# GigaVGA666PS2.net
KiCad netlist of a schematic drawn in EasyEDA Pro
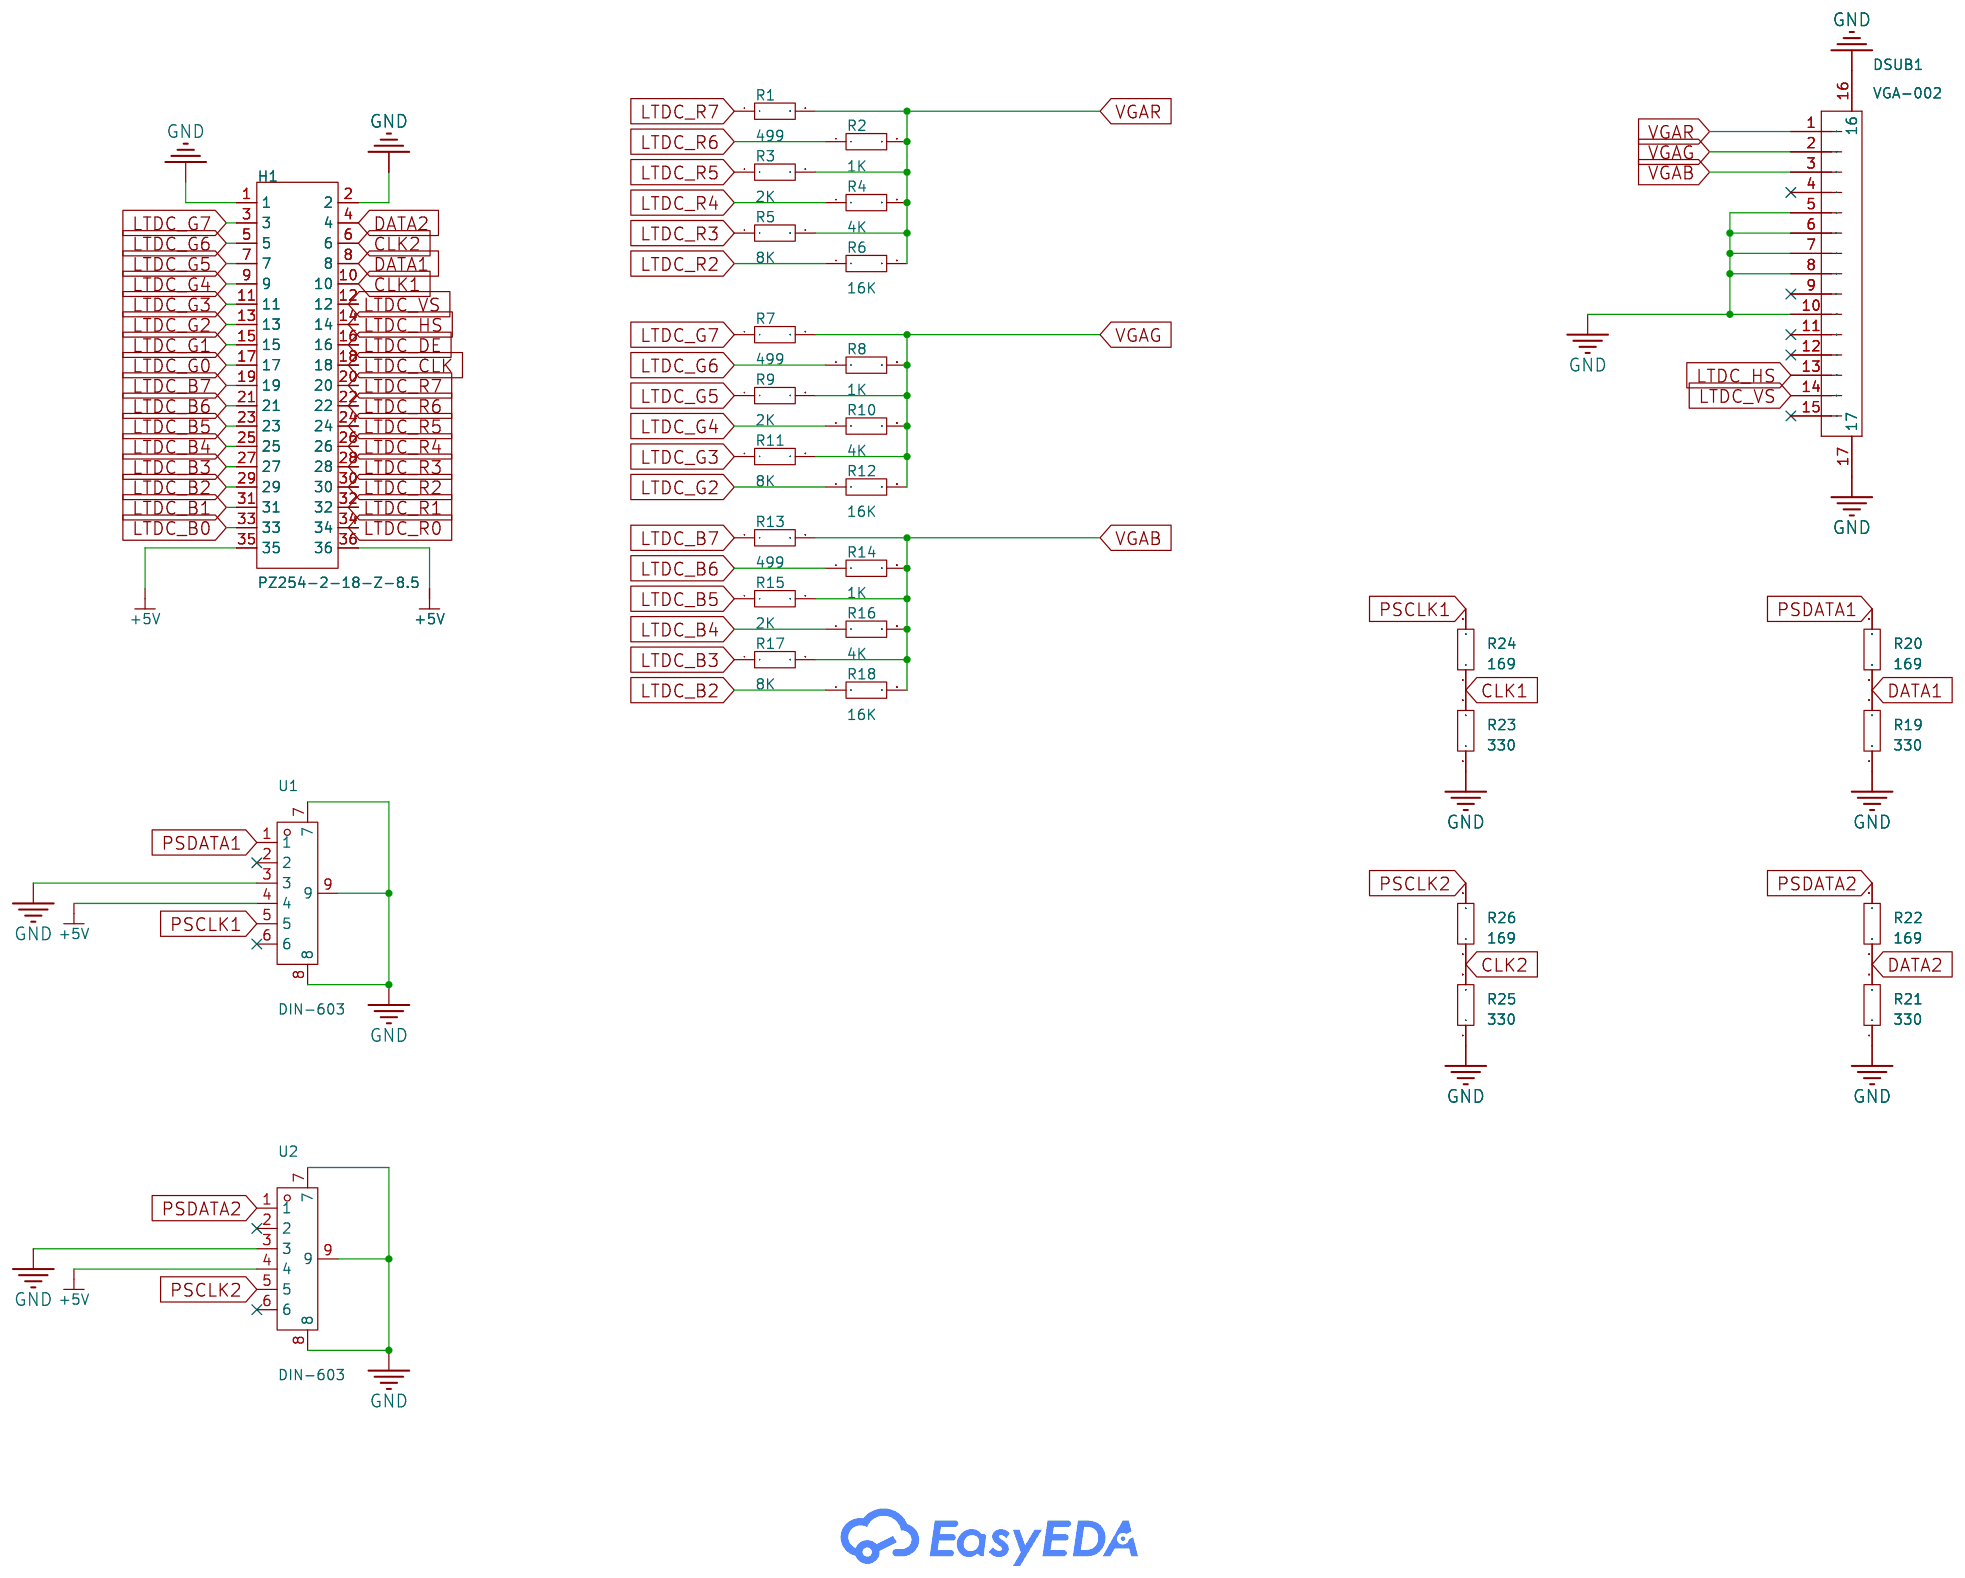
[diagram p0: schematic sheet]

(export (version "E")
  (design (tool "Eeschema 10.0.6"))
  (components
    (comp (ref "DSUB1")
      (value "VGA-002")
      (footprint "easyedapro:D-SUB-TH_VGA-002")
      (fields (field (name "Manufacturer") "BOOMELE(博穆精密)"))
      (libsource (lib "easyedapro") (part "VGA-002"))
    )
    (comp (ref "H1")
      (value "PZ254-2-18-Z-8.5")
      (footprint "easyedapro:HDR-TH_36P-P2.54-V-M-R2-C18-S2.54")
      (fields (field (name "Manufacturer") "HCTL(华灿天禄)"))
      (libsource (lib "easyedapro") (part "PZ254-2-18-Z-8.5"))
    )
    (comp (ref "R1") (value "499") (footprint "easyedapro:R0603") (libsource (lib "easyedapro") (part "Res")))
    (comp (ref "R2") (value "1K") (footprint "easyedapro:R0603") (libsource (lib "easyedapro") (part "Res")))
    (comp (ref "R3") (value "2K") (footprint "easyedapro:R0603") (libsource (lib "easyedapro") (part "Res")))
    (comp (ref "R4") (value "4K") (footprint "easyedapro:R0603") (libsource (lib "easyedapro") (part "Res")))
    (comp (ref "R5") (value "8K") (footprint "easyedapro:R0603") (libsource (lib "easyedapro") (part "Res")))
    (comp (ref "R6") (value "16K") (footprint "easyedapro:R0603") (libsource (lib "easyedapro") (part "Res")))
    (comp (ref "R7") (value "499") (footprint "easyedapro:R0603") (libsource (lib "easyedapro") (part "Res")))
    (comp (ref "R8") (value "1K") (footprint "easyedapro:R0603") (libsource (lib "easyedapro") (part "Res")))
    (comp (ref "R9") (value "2K") (footprint "easyedapro:R0603") (libsource (lib "easyedapro") (part "Res")))
    (comp (ref "R10") (value "4K") (footprint "easyedapro:R0603") (libsource (lib "easyedapro") (part "Res")))
    (comp (ref "R11") (value "8K") (footprint "easyedapro:R0603") (libsource (lib "easyedapro") (part "Res")))
    (comp (ref "R12")
      (value "16K")
      (footprint "easyedapro:R0603")
      (libsource (lib "easyedapro") (part "Res"))
    )
    (comp (ref "R13")
      (value "499")
      (footprint "easyedapro:R0603")
      (libsource (lib "easyedapro") (part "Res"))
    )
    (comp (ref "R14") (value "1K") (footprint "easyedapro:R0603") (libsource (lib "easyedapro") (part "Res")))
    (comp (ref "R15") (value "2K") (footprint "easyedapro:R0603") (libsource (lib "easyedapro") (part "Res")))
    (comp (ref "R16") (value "4K") (footprint "easyedapro:R0603") (libsource (lib "easyedapro") (part "Res")))
    (comp (ref "R17") (value "8K") (footprint "easyedapro:R0603") (libsource (lib "easyedapro") (part "Res")))
    (comp (ref "R18")
      (value "16K")
      (footprint "easyedapro:R0603")
      (libsource (lib "easyedapro") (part "Res"))
    )
    (comp (ref "R19")
      (value "330")
      (footprint "easyedapro:R0603")
      (libsource (lib "easyedapro") (part "Res"))
    )
    (comp (ref "R20")
      (value "169")
      (footprint "easyedapro:R0603")
      (libsource (lib "easyedapro") (part "Res"))
    )
    (comp (ref "R21")
      (value "330")
      (footprint "easyedapro:R0603")
      (libsource (lib "easyedapro") (part "Res"))
    )
    (comp (ref "R22")
      (value "169")
      (footprint "easyedapro:R0603")
      (libsource (lib "easyedapro") (part "Res"))
    )
    (comp (ref "R23")
      (value "330")
      (footprint "easyedapro:R0603")
      (libsource (lib "easyedapro") (part "Res"))
    )
    (comp (ref "R24")
      (value "169")
      (footprint "easyedapro:R0603")
      (libsource (lib "easyedapro") (part "Res"))
    )
    (comp (ref "R25")
      (value "330")
      (footprint "easyedapro:R0603")
      (libsource (lib "easyedapro") (part "Res"))
    )
    (comp (ref "R26")
      (value "169")
      (footprint "easyedapro:R0603")
      (libsource (lib "easyedapro") (part "Res"))
    )
    (comp (ref "U1")
      (value "DIN-603")
      (footprint "easyedapro:PS2-TH_DIN-603")
      (fields (field (name "Manufacturer") "Legion(六钧)"))
      (libsource (lib "easyedapro") (part "DIN-603_C23689424"))
    )
    (comp (ref "U2")
      (value "DIN-603")
      (footprint "easyedapro:PS2-TH_DIN-603")
      (fields (field (name "Manufacturer") "Legion(六钧)"))
      (libsource (lib "easyedapro") (part "DIN-603_C23689424"))
    )
  )
  (nets
    (net (code "1") (name "+5V") (class "Default")
      (node (ref "H1") (pin "35") (pinfunction "35_35") (pintype "unspecified"))
      (node (ref "H1") (pin "36") (pinfunction "36_36") (pintype "unspecified"))
      (node (ref "U1") (pin "4") (pinfunction "4_4") (pintype "unspecified"))
      (node (ref "U2") (pin "4") (pinfunction "4_4") (pintype "unspecified"))
    )
    (net (code "2") (name "CLK1") (class "Default")
      (node (ref "H1") (pin "10") (pinfunction "10_10") (pintype "unspecified"))
      (node (ref "R23") (pin "2") (pinfunction "2_2") (pintype "input"))
      (node (ref "R24") (pin "1") (pinfunction "1_1") (pintype "input"))
    )
    (net (code "3") (name "CLK2") (class "Default")
      (node (ref "H1") (pin "6") (pinfunction "6_6") (pintype "unspecified"))
      (node (ref "R25") (pin "2") (pinfunction "2_2") (pintype "input"))
      (node (ref "R26") (pin "1") (pinfunction "1_1") (pintype "input"))
    )
    (net (code "4") (name "DATA1") (class "Default")
      (node (ref "H1") (pin "8") (pinfunction "8_8") (pintype "unspecified"))
      (node (ref "R19") (pin "2") (pinfunction "2_2") (pintype "input"))
      (node (ref "R20") (pin "1") (pinfunction "1_1") (pintype "input"))
    )
    (net (code "5") (name "DATA2") (class "Default")
      (node (ref "H1") (pin "4") (pinfunction "4_4") (pintype "unspecified"))
      (node (ref "R21") (pin "2") (pinfunction "2_2") (pintype "input"))
      (node (ref "R22") (pin "1") (pinfunction "1_1") (pintype "input"))
    )
    (net (code "6") (name "GND") (class "Default")
      (node (ref "DSUB1") (pin "10") (pinfunction "10_10") (pintype "unspecified"))
      (node (ref "DSUB1") (pin "16") (pinfunction "16_16") (pintype "unspecified"))
      (node (ref "DSUB1") (pin "17") (pinfunction "17_17") (pintype "unspecified"))
      (node (ref "DSUB1") (pin "5") (pinfunction "5_5") (pintype "unspecified"))
      (node (ref "DSUB1") (pin "6") (pinfunction "6_6") (pintype "unspecified"))
      (node (ref "DSUB1") (pin "7") (pinfunction "7_7") (pintype "unspecified"))
      (node (ref "DSUB1") (pin "8") (pinfunction "8_8") (pintype "unspecified"))
      (node (ref "H1") (pin "1") (pinfunction "1_1") (pintype "unspecified"))
      (node (ref "H1") (pin "2") (pinfunction "2_2") (pintype "unspecified"))
      (node (ref "R19") (pin "1") (pinfunction "1_1") (pintype "input"))
      (node (ref "R21") (pin "1") (pinfunction "1_1") (pintype "input"))
      (node (ref "R23") (pin "1") (pinfunction "1_1") (pintype "input"))
      (node (ref "R25") (pin "1") (pinfunction "1_1") (pintype "input"))
      (node (ref "U1") (pin "3") (pinfunction "3_3") (pintype "unspecified"))
      (node (ref "U1") (pin "7") (pinfunction "7_7") (pintype "unspecified"))
      (node (ref "U1") (pin "8") (pinfunction "8_8") (pintype "unspecified"))
      (node (ref "U1") (pin "9") (pinfunction "9_9") (pintype "unspecified"))
      (node (ref "U2") (pin "3") (pinfunction "3_3") (pintype "unspecified"))
      (node (ref "U2") (pin "7") (pinfunction "7_7") (pintype "unspecified"))
      (node (ref "U2") (pin "8") (pinfunction "8_8") (pintype "unspecified"))
      (node (ref "U2") (pin "9") (pinfunction "9_9") (pintype "unspecified"))
    )
    (net (code "7") (name "LTDC_B0") (class "Default")
      (node (ref "H1") (pin "33") (pinfunction "33_33") (pintype "unspecified"))
    )
    (net (code "8") (name "LTDC_B1") (class "Default")
      (node (ref "H1") (pin "31") (pinfunction "31_31") (pintype "unspecified"))
    )
    (net (code "9") (name "LTDC_B2") (class "Default")
      (node (ref "H1") (pin "29") (pinfunction "29_29") (pintype "unspecified"))
      (node (ref "R18") (pin "1") (pinfunction "1_1") (pintype "input"))
    )
    (net (code "10") (name "LTDC_B3") (class "Default")
      (node (ref "H1") (pin "27") (pinfunction "27_27") (pintype "unspecified"))
      (node (ref "R17") (pin "1") (pinfunction "1_1") (pintype "input"))
    )
    (net (code "11") (name "LTDC_B4") (class "Default")
      (node (ref "H1") (pin "25") (pinfunction "25_25") (pintype "unspecified"))
      (node (ref "R16") (pin "1") (pinfunction "1_1") (pintype "input"))
    )
    (net (code "12") (name "LTDC_B5") (class "Default")
      (node (ref "H1") (pin "23") (pinfunction "23_23") (pintype "unspecified"))
      (node (ref "R15") (pin "1") (pinfunction "1_1") (pintype "input"))
    )
    (net (code "13") (name "LTDC_B6") (class "Default")
      (node (ref "H1") (pin "21") (pinfunction "21_21") (pintype "unspecified"))
      (node (ref "R14") (pin "1") (pinfunction "1_1") (pintype "input"))
    )
    (net (code "14") (name "LTDC_B7") (class "Default")
      (node (ref "H1") (pin "19") (pinfunction "19_19") (pintype "unspecified"))
      (node (ref "R13") (pin "1") (pinfunction "1_1") (pintype "input"))
    )
    (net (code "15") (name "LTDC_CLK") (class "Default")
      (node (ref "H1") (pin "18") (pinfunction "18_18") (pintype "unspecified"))
    )
    (net (code "16") (name "LTDC_DE") (class "Default")
      (node (ref "H1") (pin "16") (pinfunction "16_16") (pintype "unspecified"))
    )
    (net (code "17") (name "LTDC_G0") (class "Default")
      (node (ref "H1") (pin "17") (pinfunction "17_17") (pintype "unspecified"))
    )
    (net (code "18") (name "LTDC_G1") (class "Default")
      (node (ref "H1") (pin "15") (pinfunction "15_15") (pintype "unspecified"))
    )
    (net (code "19") (name "LTDC_G2") (class "Default")
      (node (ref "H1") (pin "13") (pinfunction "13_13") (pintype "unspecified"))
      (node (ref "R12") (pin "1") (pinfunction "1_1") (pintype "input"))
    )
    (net (code "20") (name "LTDC_G3") (class "Default")
      (node (ref "H1") (pin "11") (pinfunction "11_11") (pintype "unspecified"))
      (node (ref "R11") (pin "1") (pinfunction "1_1") (pintype "input"))
    )
    (net (code "21") (name "LTDC_G4") (class "Default")
      (node (ref "H1") (pin "9") (pinfunction "9_9") (pintype "unspecified"))
      (node (ref "R10") (pin "1") (pinfunction "1_1") (pintype "input"))
    )
    (net (code "22") (name "LTDC_G5") (class "Default")
      (node (ref "H1") (pin "7") (pinfunction "7_7") (pintype "unspecified"))
      (node (ref "R9") (pin "1") (pinfunction "1_1") (pintype "input"))
    )
    (net (code "23") (name "LTDC_G6") (class "Default")
      (node (ref "H1") (pin "5") (pinfunction "5_5") (pintype "unspecified"))
      (node (ref "R8") (pin "1") (pinfunction "1_1") (pintype "input"))
    )
    (net (code "24") (name "LTDC_G7") (class "Default")
      (node (ref "H1") (pin "3") (pinfunction "3_3") (pintype "unspecified"))
      (node (ref "R7") (pin "1") (pinfunction "1_1") (pintype "input"))
    )
    (net (code "25") (name "LTDC_HS") (class "Default")
      (node (ref "DSUB1") (pin "13") (pinfunction "13_13") (pintype "unspecified"))
      (node (ref "H1") (pin "14") (pinfunction "14_14") (pintype "unspecified"))
    )
    (net (code "26") (name "LTDC_R0") (class "Default")
      (node (ref "H1") (pin "34") (pinfunction "34_34") (pintype "unspecified"))
    )
    (net (code "27") (name "LTDC_R1") (class "Default")
      (node (ref "H1") (pin "32") (pinfunction "32_32") (pintype "unspecified"))
    )
    (net (code "28") (name "LTDC_R2") (class "Default")
      (node (ref "H1") (pin "30") (pinfunction "30_30") (pintype "unspecified"))
      (node (ref "R6") (pin "1") (pinfunction "1_1") (pintype "input"))
    )
    (net (code "29") (name "LTDC_R3") (class "Default")
      (node (ref "H1") (pin "28") (pinfunction "28_28") (pintype "unspecified"))
      (node (ref "R5") (pin "1") (pinfunction "1_1") (pintype "input"))
    )
    (net (code "30") (name "LTDC_R4") (class "Default")
      (node (ref "H1") (pin "26") (pinfunction "26_26") (pintype "unspecified"))
      (node (ref "R4") (pin "1") (pinfunction "1_1") (pintype "input"))
    )
    (net (code "31") (name "LTDC_R5") (class "Default")
      (node (ref "H1") (pin "24") (pinfunction "24_24") (pintype "unspecified"))
      (node (ref "R3") (pin "1") (pinfunction "1_1") (pintype "input"))
    )
    (net (code "32") (name "LTDC_R6") (class "Default")
      (node (ref "H1") (pin "22") (pinfunction "22_22") (pintype "unspecified"))
      (node (ref "R2") (pin "1") (pinfunction "1_1") (pintype "input"))
    )
    (net (code "33") (name "LTDC_R7") (class "Default")
      (node (ref "H1") (pin "20") (pinfunction "20_20") (pintype "unspecified"))
      (node (ref "R1") (pin "1") (pinfunction "1_1") (pintype "input"))
    )
    (net (code "34") (name "LTDC_VS") (class "Default")
      (node (ref "DSUB1") (pin "14") (pinfunction "14_14") (pintype "unspecified"))
      (node (ref "H1") (pin "12") (pinfunction "12_12") (pintype "unspecified"))
    )
    (net (code "35") (name "PSCLK1") (class "Default")
      (node (ref "R24") (pin "2") (pinfunction "2_2") (pintype "input"))
      (node (ref "U1") (pin "5") (pinfunction "5_5") (pintype "unspecified"))
    )
    (net (code "36") (name "PSCLK2") (class "Default")
      (node (ref "R26") (pin "2") (pinfunction "2_2") (pintype "input"))
      (node (ref "U2") (pin "5") (pinfunction "5_5") (pintype "unspecified"))
    )
    (net (code "37") (name "PSDATA1") (class "Default")
      (node (ref "R20") (pin "2") (pinfunction "2_2") (pintype "input"))
      (node (ref "U1") (pin "1") (pinfunction "1_1") (pintype "unspecified"))
    )
    (net (code "38") (name "PSDATA2") (class "Default")
      (node (ref "R22") (pin "2") (pinfunction "2_2") (pintype "input"))
      (node (ref "U2") (pin "1") (pinfunction "1_1") (pintype "unspecified"))
    )
    (net (code "39") (name "VGAB") (class "Default")
      (node (ref "DSUB1") (pin "3") (pinfunction "3_3") (pintype "unspecified"))
      (node (ref "R13") (pin "2") (pinfunction "2_2") (pintype "input"))
      (node (ref "R14") (pin "2") (pinfunction "2_2") (pintype "input"))
      (node (ref "R15") (pin "2") (pinfunction "2_2") (pintype "input"))
      (node (ref "R16") (pin "2") (pinfunction "2_2") (pintype "input"))
      (node (ref "R17") (pin "2") (pinfunction "2_2") (pintype "input"))
      (node (ref "R18") (pin "2") (pinfunction "2_2") (pintype "input"))
    )
    (net (code "40") (name "VGAG") (class "Default")
      (node (ref "DSUB1") (pin "2") (pinfunction "2_2") (pintype "unspecified"))
      (node (ref "R10") (pin "2") (pinfunction "2_2") (pintype "input"))
      (node (ref "R11") (pin "2") (pinfunction "2_2") (pintype "input"))
      (node (ref "R12") (pin "2") (pinfunction "2_2") (pintype "input"))
      (node (ref "R7") (pin "2") (pinfunction "2_2") (pintype "input"))
      (node (ref "R8") (pin "2") (pinfunction "2_2") (pintype "input"))
      (node (ref "R9") (pin "2") (pinfunction "2_2") (pintype "input"))
    )
    (net (code "41") (name "VGAR") (class "Default")
      (node (ref "DSUB1") (pin "1") (pinfunction "1_1") (pintype "unspecified"))
      (node (ref "R1") (pin "2") (pinfunction "2_2") (pintype "input"))
      (node (ref "R2") (pin "2") (pinfunction "2_2") (pintype "input"))
      (node (ref "R3") (pin "2") (pinfunction "2_2") (pintype "input"))
      (node (ref "R4") (pin "2") (pinfunction "2_2") (pintype "input"))
      (node (ref "R5") (pin "2") (pinfunction "2_2") (pintype "input"))
      (node (ref "R6") (pin "2") (pinfunction "2_2") (pintype "input"))
    )
    (net (code "42") (name "unconnected-(DSUB1-Pad4)") (class "Default")
      (node (ref "DSUB1") (pin "4") (pinfunction "4_4") (pintype "unspecified+no_connect"))
    )
    (net (code "43") (name "unconnected-(DSUB1-Pad9)") (class "Default")
      (node (ref "DSUB1") (pin "9") (pinfunction "9_9") (pintype "unspecified+no_connect"))
    )
    (net (code "44") (name "unconnected-(DSUB1-Pad11)") (class "Default")
      (node (ref "DSUB1") (pin "11") (pinfunction "11_11") (pintype "unspecified+no_connect"))
    )
    (net (code "45") (name "unconnected-(DSUB1-Pad12)") (class "Default")
      (node (ref "DSUB1") (pin "12") (pinfunction "12_12") (pintype "unspecified+no_connect"))
    )
    (net (code "46") (name "unconnected-(DSUB1-Pad15)") (class "Default")
      (node (ref "DSUB1") (pin "15") (pinfunction "15_15") (pintype "unspecified+no_connect"))
    )
    (net (code "47") (name "unconnected-(U1-Pad2)") (class "Default")
      (node (ref "U1") (pin "2") (pinfunction "2_2") (pintype "unspecified+no_connect"))
    )
    (net (code "48") (name "unconnected-(U1-Pad6)") (class "Default")
      (node (ref "U1") (pin "6") (pinfunction "6_6") (pintype "unspecified+no_connect"))
    )
    (net (code "49") (name "unconnected-(U2-Pad2)") (class "Default")
      (node (ref "U2") (pin "2") (pinfunction "2_2") (pintype "unspecified+no_connect"))
    )
    (net (code "50") (name "unconnected-(U2-Pad6)") (class "Default")
      (node (ref "U2") (pin "6") (pinfunction "6_6") (pintype "unspecified+no_connect"))
    )
  )
)
